# SDRAM.net
KiCad netlist of a schematic drawn in Altium Designer
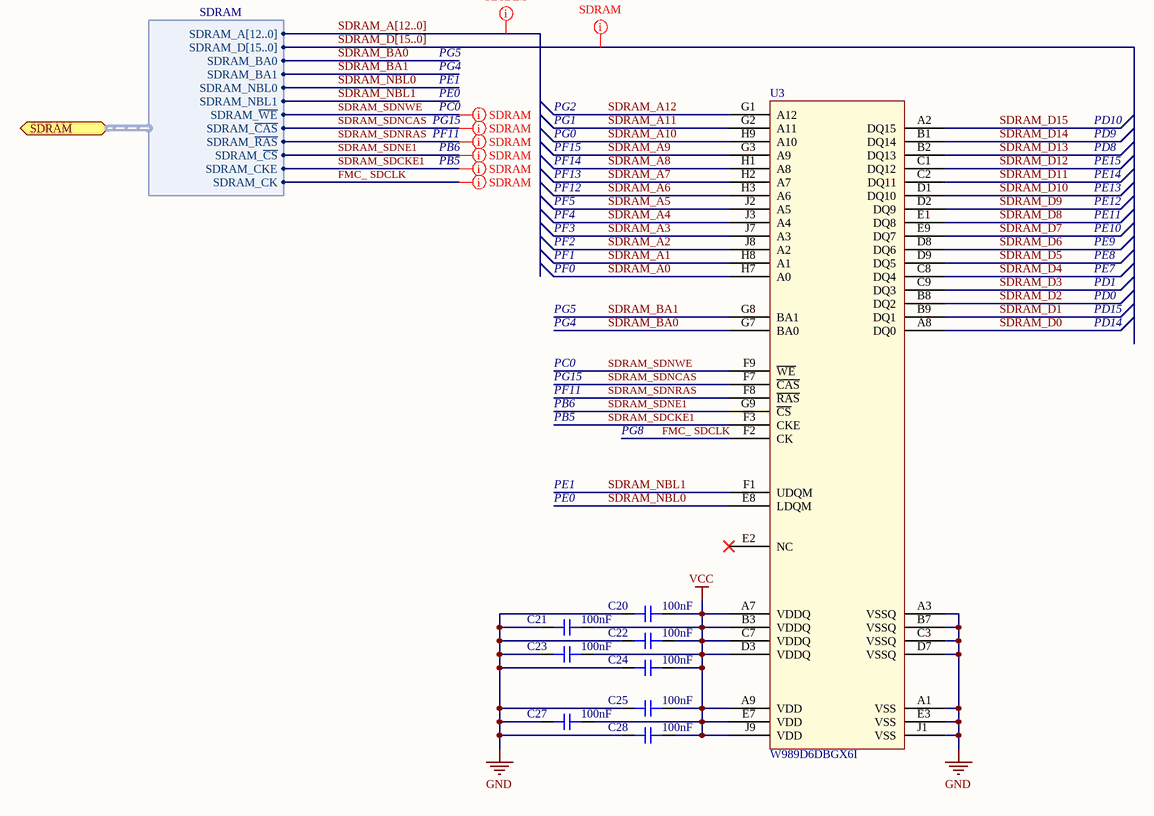
[diagram p0: SDRAM.SchDoc]

(export (version "E")
  (design (tool "Eeschema 10.0.6"))
  (components
    (comp (ref "C20")
      (value "100nF")
      (footprint "Capacitor-0603")
      (fields (field (name "Comment") "C-100nF-0603"))
      (libsource (lib "Components") (part "C-100nF-0603"))
    )
    (comp (ref "C21")
      (value "100nF")
      (footprint "Capacitor-0603")
      (fields (field (name "Comment") "C-100nF-0603"))
      (libsource (lib "Components") (part "C-100nF-0603"))
    )
    (comp (ref "C22")
      (value "100nF")
      (footprint "Capacitor-0603")
      (fields (field (name "Comment") "C-100nF-0603"))
      (libsource (lib "Components") (part "C-100nF-0603"))
    )
    (comp (ref "C23")
      (value "100nF")
      (footprint "Capacitor-0603")
      (fields (field (name "Comment") "C-100nF-0603"))
      (libsource (lib "Components") (part "C-100nF-0603"))
    )
    (comp (ref "C24")
      (value "100nF")
      (footprint "Capacitor-0603")
      (fields (field (name "Comment") "C-100nF-0603"))
      (libsource (lib "Components") (part "C-100nF-0603"))
    )
    (comp (ref "C25")
      (value "100nF")
      (footprint "Capacitor-0603")
      (fields (field (name "Comment") "C-100nF-0603"))
      (libsource (lib "Components") (part "C-100nF-0603"))
    )
    (comp (ref "C27")
      (value "100nF")
      (footprint "Capacitor-0603")
      (fields (field (name "Comment") "C-100nF-0603"))
      (libsource (lib "Components") (part "C-100nF-0603"))
    )
    (comp (ref "C28")
      (value "100nF")
      (footprint "Capacitor-0603")
      (fields (field (name "Comment") "C-100nF-0603"))
      (libsource (lib "Components") (part "C-100nF-0603"))
    )
    (comp (ref "U3")
      (value "W989D6DBGX6I")
      (footprint "W989D6DBGX6I")
      (libsource (lib "Components") (part "W989D6DBGX6I"))
    )
  )
  (nets
    (net (code "2") (name "/FMC_ SDCLK") (class "Default")
      (node (ref "U3") (pin "F2") (pinfunction "CK_F2") (pintype "passive"))
    )
    (net (code "3") (name "/SDRAM_A0") (class "Default")
      (node (ref "U3") (pin "H7") (pinfunction "A0_H7") (pintype "passive"))
    )
    (net (code "4") (name "/SDRAM_A1") (class "Default")
      (node (ref "U3") (pin "H8") (pinfunction "A1_H8") (pintype "passive"))
    )
    (net (code "5") (name "/SDRAM_A2") (class "Default")
      (node (ref "U3") (pin "J8") (pinfunction "A2_J8") (pintype "passive"))
    )
    (net (code "6") (name "/SDRAM_A3") (class "Default")
      (node (ref "U3") (pin "J7") (pinfunction "A3_J7") (pintype "passive"))
    )
    (net (code "7") (name "/SDRAM_A4") (class "Default")
      (node (ref "U3") (pin "J3") (pinfunction "A4_J3") (pintype "passive"))
    )
    (net (code "8") (name "/SDRAM_A5") (class "Default")
      (node (ref "U3") (pin "J2") (pinfunction "A5_J2") (pintype "passive"))
    )
    (net (code "9") (name "/SDRAM_A6") (class "Default")
      (node (ref "U3") (pin "H3") (pinfunction "A6_H3") (pintype "passive"))
    )
    (net (code "10") (name "/SDRAM_A7") (class "Default")
      (node (ref "U3") (pin "H2") (pinfunction "A7_H2") (pintype "passive"))
    )
    (net (code "11") (name "/SDRAM_A8") (class "Default")
      (node (ref "U3") (pin "H1") (pinfunction "A8_H1") (pintype "passive"))
    )
    (net (code "12") (name "/SDRAM_A9") (class "Default")
      (node (ref "U3") (pin "G3") (pinfunction "A9_G3") (pintype "passive"))
    )
    (net (code "13") (name "/SDRAM_A10") (class "Default")
      (node (ref "U3") (pin "H9") (pinfunction "A10_H9") (pintype "passive"))
    )
    (net (code "14") (name "/SDRAM_A11") (class "Default")
      (node (ref "U3") (pin "G2") (pinfunction "A11_G2") (pintype "passive"))
    )
    (net (code "15") (name "/SDRAM_A12") (class "Default")
      (node (ref "U3") (pin "G1") (pinfunction "A12_G1") (pintype "passive"))
    )
    (net (code "17") (name "/SDRAM_BA0") (class "Default")
      (node (ref "U3") (pin "G7") (pinfunction "BA0_G7") (pintype "passive"))
    )
    (net (code "18") (name "/SDRAM_BA1") (class "Default")
      (node (ref "U3") (pin "G8") (pinfunction "BA1_G8") (pintype "passive"))
    )
    (net (code "19") (name "/SDRAM_D0") (class "Default")
      (node (ref "U3") (pin "A8") (pinfunction "DQ0_A8") (pintype "passive"))
    )
    (net (code "20") (name "/SDRAM_D1") (class "Default")
      (node (ref "U3") (pin "B9") (pinfunction "DQ1_B9") (pintype "passive"))
    )
    (net (code "21") (name "/SDRAM_D2") (class "Default")
      (node (ref "U3") (pin "B8") (pinfunction "DQ2_B8") (pintype "passive"))
    )
    (net (code "22") (name "/SDRAM_D3") (class "Default")
      (node (ref "U3") (pin "C9") (pinfunction "DQ3_C9") (pintype "passive"))
    )
    (net (code "23") (name "/SDRAM_D4") (class "Default")
      (node (ref "U3") (pin "C8") (pinfunction "DQ4_C8") (pintype "passive"))
    )
    (net (code "24") (name "/SDRAM_D5") (class "Default")
      (node (ref "U3") (pin "D9") (pinfunction "DQ5_D9") (pintype "passive"))
    )
    (net (code "25") (name "/SDRAM_D6") (class "Default")
      (node (ref "U3") (pin "D8") (pinfunction "DQ6_D8") (pintype "passive"))
    )
    (net (code "26") (name "/SDRAM_D7") (class "Default")
      (node (ref "U3") (pin "E9") (pinfunction "DQ7_E9") (pintype "passive"))
    )
    (net (code "27") (name "/SDRAM_D8") (class "Default")
      (node (ref "U3") (pin "E1") (pinfunction "DQ8_E1") (pintype "passive"))
    )
    (net (code "28") (name "/SDRAM_D9") (class "Default")
      (node (ref "U3") (pin "D2") (pinfunction "DQ9_D2") (pintype "passive"))
    )
    (net (code "29") (name "/SDRAM_D10") (class "Default")
      (node (ref "U3") (pin "D1") (pinfunction "DQ10_D1") (pintype "passive"))
    )
    (net (code "30") (name "/SDRAM_D11") (class "Default")
      (node (ref "U3") (pin "C2") (pinfunction "DQ11_C2") (pintype "passive"))
    )
    (net (code "31") (name "/SDRAM_D12") (class "Default")
      (node (ref "U3") (pin "C1") (pinfunction "DQ12_C1") (pintype "passive"))
    )
    (net (code "32") (name "/SDRAM_D13") (class "Default")
      (node (ref "U3") (pin "B2") (pinfunction "DQ13_B2") (pintype "passive"))
    )
    (net (code "33") (name "/SDRAM_D14") (class "Default")
      (node (ref "U3") (pin "B1") (pinfunction "DQ14_B1") (pintype "passive"))
    )
    (net (code "34") (name "/SDRAM_D15") (class "Default")
      (node (ref "U3") (pin "A2") (pinfunction "DQ15_A2") (pintype "passive"))
    )
    (net (code "36") (name "/SDRAM_NBL0") (class "Default")
      (node (ref "U3") (pin "E8") (pinfunction "LDQM_E8") (pintype "passive"))
    )
    (net (code "37") (name "/SDRAM_NBL1") (class "Default")
      (node (ref "U3") (pin "F1") (pinfunction "UDQM_F1") (pintype "passive"))
    )
    (net (code "38") (name "/SDRAM_SDCKE1") (class "Default")
      (node (ref "U3") (pin "F3") (pinfunction "CKE_F3") (pintype "passive"))
    )
    (net (code "39") (name "/SDRAM_SDNCAS") (class "Default")
      (node (ref "U3") (pin "F7") (pinfunction "~{CAS}_F7") (pintype "passive"))
    )
    (net (code "40") (name "/SDRAM_SDNE1") (class "Default")
      (node (ref "U3") (pin "G9") (pinfunction "~{CS}_G9") (pintype "passive"))
    )
    (net (code "41") (name "/SDRAM_SDNRAS") (class "Default")
      (node (ref "U3") (pin "F8") (pinfunction "~{RAS}_F8") (pintype "passive"))
    )
    (net (code "42") (name "/SDRAM_SDNWE") (class "Default")
      (node (ref "U3") (pin "F9") (pinfunction "~{WE}_F9") (pintype "passive"))
    )
    (net (code "44") (name "GND") (class "Default")
      (node (ref "C20") (pin "1") (pinfunction "1_1") (pintype "passive"))
      (node (ref "C21") (pin "1") (pinfunction "1_1") (pintype "passive"))
      (node (ref "C22") (pin "1") (pinfunction "1_1") (pintype "passive"))
      (node (ref "C23") (pin "1") (pinfunction "1_1") (pintype "passive"))
      (node (ref "C24") (pin "1") (pinfunction "1_1") (pintype "passive"))
      (node (ref "C25") (pin "1") (pinfunction "1_1") (pintype "passive"))
      (node (ref "C27") (pin "1") (pinfunction "1_1") (pintype "passive"))
      (node (ref "C28") (pin "1") (pinfunction "1_1") (pintype "passive"))
      (node (ref "U3") (pin "A1") (pinfunction "VSS_A1") (pintype "passive"))
      (node (ref "U3") (pin "A3") (pinfunction "VSSQ_A3") (pintype "passive"))
      (node (ref "U3") (pin "B7") (pinfunction "VSSQ_B7") (pintype "passive"))
      (node (ref "U3") (pin "C3") (pinfunction "VSSQ_C3") (pintype "passive"))
      (node (ref "U3") (pin "D7") (pinfunction "VSSQ_D7") (pintype "passive"))
      (node (ref "U3") (pin "E3") (pinfunction "VSS_E3") (pintype "passive"))
      (node (ref "U3") (pin "J1") (pinfunction "VSS_J1") (pintype "passive"))
    )
    (net (code "45") (name "VCC") (class "Default")
      (node (ref "C20") (pin "2") (pinfunction "2_2") (pintype "passive"))
      (node (ref "C21") (pin "2") (pinfunction "2_2") (pintype "passive"))
      (node (ref "C22") (pin "2") (pinfunction "2_2") (pintype "passive"))
      (node (ref "C23") (pin "2") (pinfunction "2_2") (pintype "passive"))
      (node (ref "C24") (pin "2") (pinfunction "2_2") (pintype "passive"))
      (node (ref "C25") (pin "2") (pinfunction "2_2") (pintype "passive"))
      (node (ref "C27") (pin "2") (pinfunction "2_2") (pintype "passive"))
      (node (ref "C28") (pin "2") (pinfunction "2_2") (pintype "passive"))
      (node (ref "U3") (pin "A7") (pinfunction "VDDQ_A7") (pintype "passive"))
      (node (ref "U3") (pin "A9") (pinfunction "VDD_A9") (pintype "passive"))
      (node (ref "U3") (pin "B3") (pinfunction "VDDQ_B3") (pintype "passive"))
      (node (ref "U3") (pin "C7") (pinfunction "VDDQ_C7") (pintype "passive"))
      (node (ref "U3") (pin "D3") (pinfunction "VDDQ_D3") (pintype "passive"))
      (node (ref "U3") (pin "E7") (pinfunction "VDD_E7") (pintype "passive"))
      (node (ref "U3") (pin "J9") (pinfunction "VDD_J9") (pintype "passive"))
    )
    (net (code "46") (name "unconnected-(U3-NC-PadE2)") (class "Default")
      (node (ref "U3") (pin "E2") (pinfunction "NC_E2") (pintype "passive+no_connect"))
    )
  )
)
